# Master.net
KiCad netlist of a schematic drawn in Altium Designer
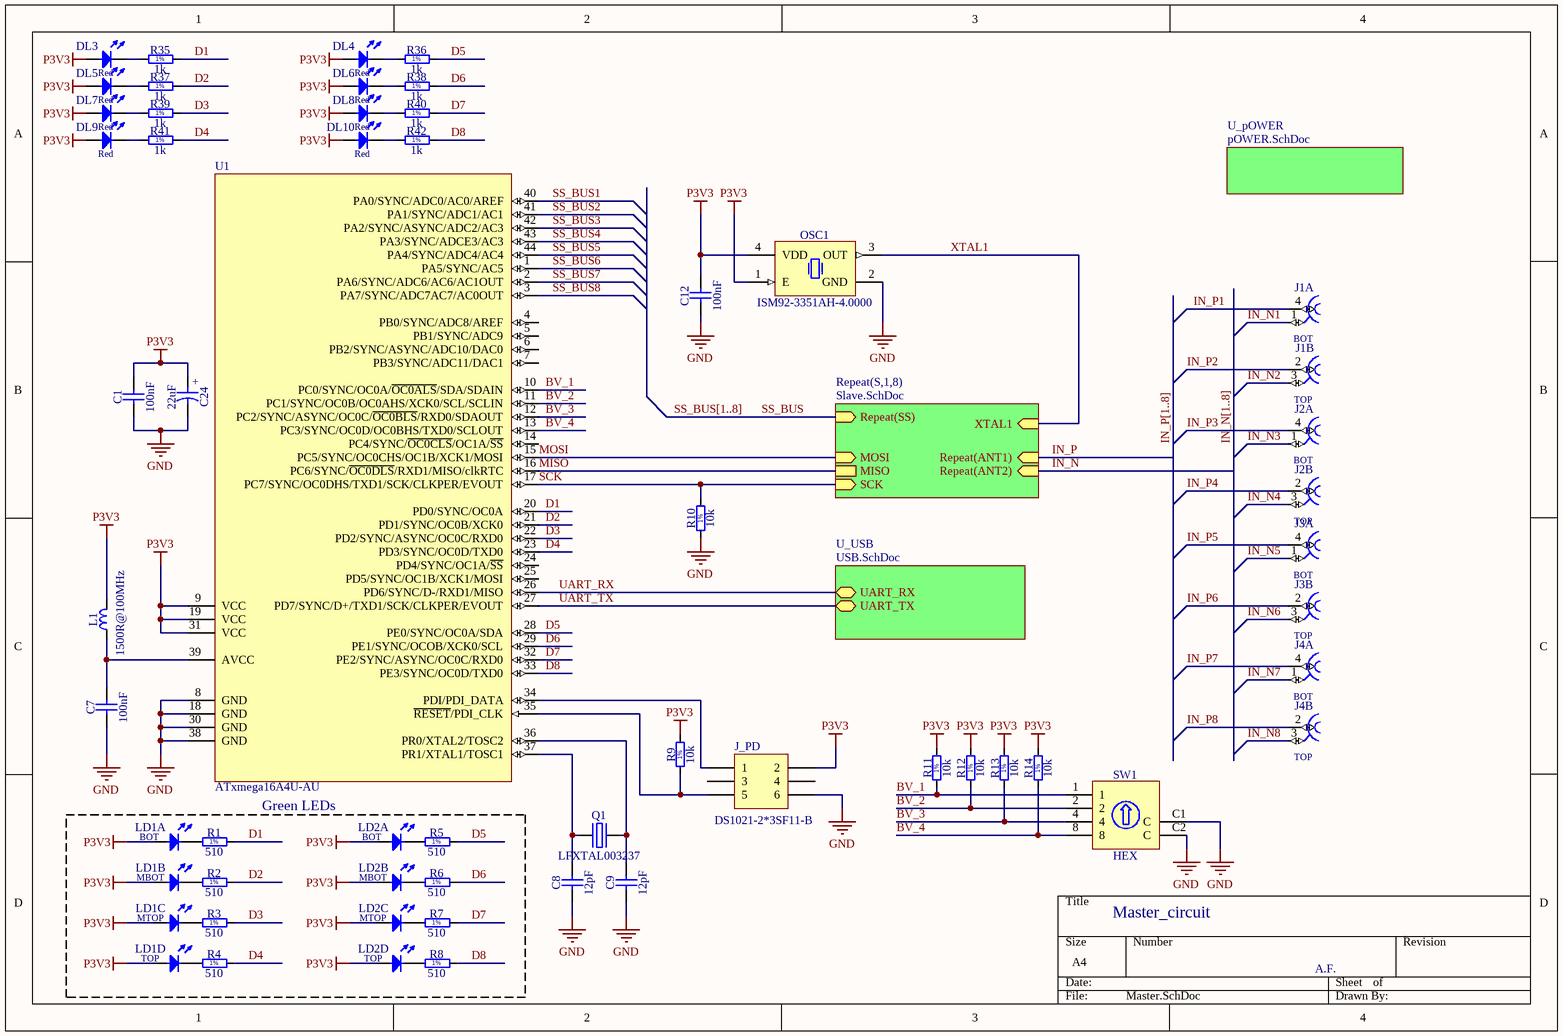
[diagram p0: Master.SchDoc]

(export (version "E")
  (design (tool "Eeschema 10.0.6"))
  (components
    (comp (ref "C1")
      (value "100nF")
      (footprint "CAPC1608X87N")
      (description "Non-polarised capacitor")
      (fields
        (field (name "PART NUMBER") "CC0603_100NF_50V_10%_X5R")
        (field (name "VOLTAGE") "50V")
        (field (name "AUTHOR") "CERN DEM MR")
      )
      (libsource (lib "Capacitors") (part "Capacitor - non polarized"))
    )
    (comp (ref "C7")
      (value "100nF")
      (footprint "CAPC1608X87N")
      (description "Non-polarised capacitor")
      (fields
        (field (name "PART NUMBER") "CC0603_100NF_50V_10%_X5R")
        (field (name "VOLTAGE") "50V")
        (field (name "AUTHOR") "CERN DEM MR")
      )
      (libsource (lib "Capacitors") (part "Capacitor - non polarized"))
    )
    (comp (ref "C8")
      (value "12pF")
      (footprint "CAPC1608X87N")
      (description "Non-polarised capacitor")
      (fields
        (field (name "PART NUMBER") "CC0603_12PF_50V_5%_NP0")
        (field (name "VOLTAGE") "50V")
        (field (name "AUTHOR") "CERN DEM JLC")
      )
      (libsource (lib "Capacitors") (part "Capacitor - non polarized"))
    )
    (comp (ref "C9")
      (value "12pF")
      (footprint "CAPC1608X87N")
      (description "Non-polarised capacitor")
      (fields
        (field (name "PART NUMBER") "CC0603_12PF_50V_5%_NP0")
        (field (name "VOLTAGE") "50V")
        (field (name "AUTHOR") "CERN DEM JLC")
      )
      (libsource (lib "Capacitors") (part "Capacitor - non polarized"))
    )
    (comp (ref "C12")
      (value "100nF")
      (footprint "CAPC1608X87N")
      (description "Non-polarised capacitor")
      (fields
        (field (name "PART NUMBER") "CC0603_100NF_50V_10%_X5R")
        (field (name "VOLTAGE") "50V")
        (field (name "AUTHOR") "CERN DEM MR")
      )
      (libsource (lib "Capacitors") (part "Capacitor - non polarized"))
    )
    (comp (ref "C24")
      (value "22uF")
      (footprint "CAPAE430X540N")
      (description "Polarised capacitor")
      (fields
        (field (name "PART NUMBER") "CAE430-540_22UF_10V_20%")
        (field (name "VOLTAGE") "10V")
        (field (name "AUTHOR") "CERN DEM JLC")
      )
      (libsource (lib "Capacitors") (part "Capacitor - polarized"))
    )
    (comp (ref "DL3")
      (value "Red")
      (footprint "LED_OSRAM_LSR976")
      (description "LED Red 1C 2A")
      (fields
        (field (name "PART NUMBER") "LS R976-NR-1")
        (field (name "MANUFACTURER") "OSRAM")
        (field (name "AUTHOR") "CERN DEM JLC")
      )
      (libsource (lib "ICs And Semiconductors") (part "LED Red 1C 2A"))
    )
    (comp (ref "DL4")
      (value "Red")
      (footprint "LED_OSRAM_LSR976")
      (description "LED Red 1C 2A")
      (fields
        (field (name "PART NUMBER") "LS R976-NR-1")
        (field (name "MANUFACTURER") "OSRAM")
        (field (name "AUTHOR") "CERN DEM JLC")
      )
      (libsource (lib "ICs And Semiconductors") (part "LED Red 1C 2A"))
    )
    (comp (ref "DL5")
      (value "Red")
      (footprint "LED_OSRAM_LSR976")
      (description "LED Red 1C 2A")
      (fields
        (field (name "PART NUMBER") "LS R976-NR-1")
        (field (name "MANUFACTURER") "OSRAM")
        (field (name "AUTHOR") "CERN DEM JLC")
      )
      (libsource (lib "ICs And Semiconductors") (part "LED Red 1C 2A"))
    )
    (comp (ref "DL6")
      (value "Red")
      (footprint "LED_OSRAM_LSR976")
      (description "LED Red 1C 2A")
      (fields
        (field (name "PART NUMBER") "LS R976-NR-1")
        (field (name "MANUFACTURER") "OSRAM")
        (field (name "AUTHOR") "CERN DEM JLC")
      )
      (libsource (lib "ICs And Semiconductors") (part "LED Red 1C 2A"))
    )
    (comp (ref "DL7")
      (value "Red")
      (footprint "LED_OSRAM_LSR976")
      (description "LED Red 1C 2A")
      (fields
        (field (name "PART NUMBER") "LS R976-NR-1")
        (field (name "MANUFACTURER") "OSRAM")
        (field (name "AUTHOR") "CERN DEM JLC")
      )
      (libsource (lib "ICs And Semiconductors") (part "LED Red 1C 2A"))
    )
    (comp (ref "DL8")
      (value "Red")
      (footprint "LED_OSRAM_LSR976")
      (description "LED Red 1C 2A")
      (fields
        (field (name "PART NUMBER") "LS R976-NR-1")
        (field (name "MANUFACTURER") "OSRAM")
        (field (name "AUTHOR") "CERN DEM JLC")
      )
      (libsource (lib "ICs And Semiconductors") (part "LED Red 1C 2A"))
    )
    (comp (ref "DL9")
      (value "Red")
      (footprint "LED_OSRAM_LSR976")
      (description "LED Red 1C 2A")
      (fields
        (field (name "PART NUMBER") "LS R976-NR-1")
        (field (name "MANUFACTURER") "OSRAM")
        (field (name "AUTHOR") "CERN DEM JLC")
      )
      (libsource (lib "ICs And Semiconductors") (part "LED Red 1C 2A"))
    )
    (comp (ref "DL10")
      (value "Red")
      (footprint "LED_OSRAM_LSR976")
      (description "LED Red 1C 2A")
      (fields
        (field (name "PART NUMBER") "LS R976-NR-1")
        (field (name "MANUFACTURER") "OSRAM")
        (field (name "AUTHOR") "CERN DEM JLC")
      )
      (libsource (lib "ICs And Semiconductors") (part "LED Red 1C 2A"))
    )
    (comp (ref "J1")
      (value "Family")
      (footprint "RENHOTEC_RHT-610-0049")
      (description "Dual Right Angle 50 Ohm BNC Jack, White Valox Case")
      (fields
        (field (name "PART NUMBER") "RENHOTEC_RHT-610-0049")
        (field (name "MANUFACTURER") "RENHOTEC")
        (field (name "AUTHOR") "GK")
      )
      (libsource (lib "LIBRARY_SCH") (part "CON_BNC_DUAL"))
    )
    (comp (ref "J2")
      (value "Family")
      (footprint "RENHOTEC_RHT-610-0049")
      (description "Dual Right Angle 50 Ohm BNC Jack, White Valox Case")
      (fields
        (field (name "PART NUMBER") "RENHOTEC_RHT-610-0049")
        (field (name "MANUFACTURER") "RENHOTEC")
        (field (name "AUTHOR") "GK")
      )
      (libsource (lib "LIBRARY_SCH") (part "CON_BNC_DUAL"))
    )
    (comp (ref "J3")
      (value "Family")
      (footprint "RENHOTEC_RHT-610-0049")
      (description "Dual Right Angle 50 Ohm BNC Jack, White Valox Case")
      (fields
        (field (name "PART NUMBER") "RENHOTEC_RHT-610-0049")
        (field (name "MANUFACTURER") "RENHOTEC")
        (field (name "AUTHOR") "GK")
      )
      (libsource (lib "LIBRARY_SCH") (part "CON_BNC_DUAL"))
    )
    (comp (ref "J4")
      (value "Family")
      (footprint "RENHOTEC_RHT-610-0049")
      (description "Dual Right Angle 50 Ohm BNC Jack, White Valox Case")
      (fields
        (field (name "PART NUMBER") "RENHOTEC_RHT-610-0049")
        (field (name "MANUFACTURER") "RENHOTEC")
        (field (name "AUTHOR") "GK")
      )
      (libsource (lib "LIBRARY_SCH") (part "CON_BNC_DUAL"))
    )
    (comp (ref "J_PD")
      (value "DS1021-2*3SF11-B")
      (footprint "HDR2X3")
      (description "THT Header, 6-Pin, Dual row, 2.54mm pitch")
      (fields (field (name "MANUFACTURER") "CONNFLY") (field (name "PUBLISHER") "Altium Limited"))
      (libsource (lib "Miscellaneous Connectors") (part "Header 3X2"))
    )
    (comp (ref "L1")
      (value "1500R@100MHz")
      (footprint "Miscellaneous Devices:1608[0603]")
      (description "Ferrite Bead")
      (fields
        (field (name "POWER") "0.5A")
        (field (name "MANUFACTURER") "MURATA")
        (field (name "AUTHOR") "CERN DEM BC")
      )
      (libsource (lib "altium-import") (part "root_1_Inductor_"))
    )
    (comp (ref "LD1")
      (value "H485CGDL")
      (footprint "LED_BIVAR_H485CGDL")
      (description "=Part Description")
      (fields (field (name "MANUFACTURER") "BIVAR") (field (name "AUTHOR") "CERN DEM JLC"))
      (libsource (lib "RFID_system") (part "LED x4 Green 1C2A-BOT_3C4A_5C6A_7C8A-TOP"))
    )
    (comp (ref "LD2")
      (value "H485CGDL")
      (footprint "LED_BIVAR_H485CGDL")
      (description "=Part Description")
      (fields (field (name "MANUFACTURER") "BIVAR") (field (name "AUTHOR") "CERN DEM JLC"))
      (libsource (lib "RFID_system") (part "LED x4 Green 1C2A-BOT_3C4A_5C6A_7C8A-TOP"))
    )
    (comp (ref "OSC1")
      (value "ISM92-3351AH-4.0000")
      (footprint "OSCSC250P320X500X130-4N")
      (description "Oscillator 4 pins 3.3V 4MHz")
      (fields (field (name "MANUFACTURER") "ILSI"))
      (libsource (lib "Crystals & Oscillators") (part "Oscillator 1E 2GND 3OUT 4VDD"))
    )
    (comp (ref "Q1")
      (value "LFXTAL003237")
      (footprint "XTAL1160X490X430")
      (description "=Part Description")
      (fields
        (field (name "MANUFACTURER") "IQD FREQUENCY PRODUCTS")
        (field (name "MANUFACTURER PART NUMBER") "LF XTAL003237")
        (field (name "AUTHOR") "CERN DEM MR")
      )
      (libsource (lib "ICs And Semiconductors") (part "Quartz Crystal"))
    )
    (comp (ref "R1")
      (value "510")
      (footprint "RESC1608X55N")
      (description "Resistor - 1%")
      (fields
        (field (name "PART NUMBER") "R0603_510R_1%_0.1W_100PPM")
        (field (name "POWER") "0.1W")
        (field (name "AUTHOR") "CERN DEM JLC")
      )
      (libsource (lib "Resistors") (part "Resistor - 1%"))
    )
    (comp (ref "R2")
      (value "510")
      (footprint "RESC1608X55N")
      (description "Resistor - 1%")
      (fields
        (field (name "PART NUMBER") "R0603_510R_1%_0.1W_100PPM")
        (field (name "POWER") "0.1W")
        (field (name "AUTHOR") "CERN DEM JLC")
      )
      (libsource (lib "Resistors") (part "Resistor - 1%"))
    )
    (comp (ref "R3")
      (value "510")
      (footprint "RESC1608X55N")
      (description "Resistor - 1%")
      (fields
        (field (name "PART NUMBER") "R0603_510R_1%_0.1W_100PPM")
        (field (name "POWER") "0.1W")
        (field (name "AUTHOR") "CERN DEM JLC")
      )
      (libsource (lib "Resistors") (part "Resistor - 1%"))
    )
    (comp (ref "R4")
      (value "510")
      (footprint "RESC1608X55N")
      (description "Resistor - 1%")
      (fields
        (field (name "PART NUMBER") "R0603_510R_1%_0.1W_100PPM")
        (field (name "POWER") "0.1W")
        (field (name "AUTHOR") "CERN DEM JLC")
      )
      (libsource (lib "Resistors") (part "Resistor - 1%"))
    )
    (comp (ref "R5")
      (value "510")
      (footprint "RESC1608X55N")
      (description "Resistor - 1%")
      (fields
        (field (name "PART NUMBER") "R0603_510R_1%_0.1W_100PPM")
        (field (name "POWER") "0.1W")
        (field (name "AUTHOR") "CERN DEM JLC")
      )
      (libsource (lib "Resistors") (part "Resistor - 1%"))
    )
    (comp (ref "R6")
      (value "510")
      (footprint "RESC1608X55N")
      (description "Resistor - 1%")
      (fields
        (field (name "PART NUMBER") "R0603_510R_1%_0.1W_100PPM")
        (field (name "POWER") "0.1W")
        (field (name "AUTHOR") "CERN DEM JLC")
      )
      (libsource (lib "Resistors") (part "Resistor - 1%"))
    )
    (comp (ref "R7")
      (value "510")
      (footprint "RESC1608X55N")
      (description "Resistor - 1%")
      (fields
        (field (name "PART NUMBER") "R0603_510R_1%_0.1W_100PPM")
        (field (name "POWER") "0.1W")
        (field (name "AUTHOR") "CERN DEM JLC")
      )
      (libsource (lib "Resistors") (part "Resistor - 1%"))
    )
    (comp (ref "R8")
      (value "510")
      (footprint "RESC1608X55N")
      (description "Resistor - 1%")
      (fields
        (field (name "PART NUMBER") "R0603_510R_1%_0.1W_100PPM")
        (field (name "POWER") "0.1W")
        (field (name "AUTHOR") "CERN DEM JLC")
      )
      (libsource (lib "Resistors") (part "Resistor - 1%"))
    )
    (comp (ref "R9")
      (value "10k")
      (footprint "RESC1608X55N")
      (description "Resistor - 1%")
      (fields
        (field (name "PART NUMBER") "R0603_10K_1%_0.1W_100PPM")
        (field (name "POWER") "0.1W")
        (field (name "AUTHOR") "CERN DEM JLC")
      )
      (libsource (lib "Resistors") (part "Resistor - 1%"))
    )
    (comp (ref "R10")
      (value "10k")
      (footprint "RESC1608X55N")
      (description "Resistor - 1%")
      (fields
        (field (name "PART NUMBER") "R0603_10K_1%_0.1W_100PPM")
        (field (name "POWER") "0.1W")
        (field (name "AUTHOR") "CERN DEM JLC")
      )
      (libsource (lib "Resistors") (part "Resistor - 1%"))
    )
    (comp (ref "R11")
      (value "10k")
      (footprint "RESC1608X55N")
      (description "Resistor - 1%")
      (fields
        (field (name "PART NUMBER") "R0603_10K_1%_0.1W_100PPM")
        (field (name "POWER") "0.1W")
        (field (name "AUTHOR") "CERN DEM JLC")
      )
      (libsource (lib "Resistors") (part "Resistor - 1%"))
    )
    (comp (ref "R12")
      (value "10k")
      (footprint "RESC1608X55N")
      (description "Resistor - 1%")
      (fields
        (field (name "PART NUMBER") "R0603_10K_1%_0.1W_100PPM")
        (field (name "POWER") "0.1W")
        (field (name "AUTHOR") "CERN DEM JLC")
      )
      (libsource (lib "Resistors") (part "Resistor - 1%"))
    )
    (comp (ref "R13")
      (value "10k")
      (footprint "RESC1608X55N")
      (description "Resistor - 1%")
      (fields
        (field (name "PART NUMBER") "R0603_10K_1%_0.1W_100PPM")
        (field (name "POWER") "0.1W")
        (field (name "AUTHOR") "CERN DEM JLC")
      )
      (libsource (lib "Resistors") (part "Resistor - 1%"))
    )
    (comp (ref "R14")
      (value "10k")
      (footprint "RESC1608X55N")
      (description "Resistor - 1%")
      (fields
        (field (name "PART NUMBER") "R0603_10K_1%_0.1W_100PPM")
        (field (name "POWER") "0.1W")
        (field (name "AUTHOR") "CERN DEM JLC")
      )
      (libsource (lib "Resistors") (part "Resistor - 1%"))
    )
    (comp (ref "R35")
      (value "1k")
      (footprint "RESC1608X50N")
      (description "Resistor - 1%")
      (fields
        (field (name "PART NUMBER") "R0805_1K_1%_0.33W_100PPM_VISHAY_CRCW-HP")
        (field (name "POWER") "0.33W")
        (field (name "AUTHOR") "CERN DEM JLC")
      )
      (libsource (lib "Resistors") (part "Resistor - 1%"))
    )
    (comp (ref "R36")
      (value "1k")
      (footprint "RESC1608X50N")
      (description "Resistor - 1%")
      (fields
        (field (name "PART NUMBER") "R0805_1K_1%_0.33W_100PPM_VISHAY_CRCW-HP")
        (field (name "POWER") "0.33W")
        (field (name "AUTHOR") "CERN DEM JLC")
      )
      (libsource (lib "Resistors") (part "Resistor - 1%"))
    )
    (comp (ref "R37")
      (value "1k")
      (footprint "RESC1608X50N")
      (description "Resistor - 1%")
      (fields
        (field (name "PART NUMBER") "R0805_1K_1%_0.33W_100PPM_VISHAY_CRCW-HP")
        (field (name "POWER") "0.33W")
        (field (name "AUTHOR") "CERN DEM JLC")
      )
      (libsource (lib "Resistors") (part "Resistor - 1%"))
    )
    (comp (ref "R38")
      (value "1k")
      (footprint "RESC1608X50N")
      (description "Resistor - 1%")
      (fields
        (field (name "PART NUMBER") "R0805_1K_1%_0.33W_100PPM_VISHAY_CRCW-HP")
        (field (name "POWER") "0.33W")
        (field (name "AUTHOR") "CERN DEM JLC")
      )
      (libsource (lib "Resistors") (part "Resistor - 1%"))
    )
    (comp (ref "R39")
      (value "1k")
      (footprint "RESC1608X50N")
      (description "Resistor - 1%")
      (fields
        (field (name "PART NUMBER") "R0805_1K_1%_0.33W_100PPM_VISHAY_CRCW-HP")
        (field (name "POWER") "0.33W")
        (field (name "AUTHOR") "CERN DEM JLC")
      )
      (libsource (lib "Resistors") (part "Resistor - 1%"))
    )
    (comp (ref "R40")
      (value "1k")
      (footprint "RESC1608X50N")
      (description "Resistor - 1%")
      (fields
        (field (name "PART NUMBER") "R0805_1K_1%_0.33W_100PPM_VISHAY_CRCW-HP")
        (field (name "POWER") "0.33W")
        (field (name "AUTHOR") "CERN DEM JLC")
      )
      (libsource (lib "Resistors") (part "Resistor - 1%"))
    )
    (comp (ref "R41")
      (value "1k")
      (footprint "RESC1608X50N")
      (description "Resistor - 1%")
      (fields
        (field (name "PART NUMBER") "R0805_1K_1%_0.33W_100PPM_VISHAY_CRCW-HP")
        (field (name "POWER") "0.33W")
        (field (name "AUTHOR") "CERN DEM JLC")
      )
      (libsource (lib "Resistors") (part "Resistor - 1%"))
    )
    (comp (ref "R42")
      (value "1k")
      (footprint "RESC1608X50N")
      (description "Resistor - 1%")
      (fields
        (field (name "PART NUMBER") "R0805_1K_1%_0.33W_100PPM_VISHAY_CRCW-HP")
        (field (name "POWER") "0.33W")
        (field (name "AUTHOR") "CERN DEM JLC")
      )
      (libsource (lib "Resistors") (part "Resistor - 1%"))
    )
    (comp (ref "SW1")
      (value "HEX")
      (footprint "SW_OMRON_A6RV-162RF")
      (description "Rotary Code Switch 1 2 4 8 C1 C2")
      (fields
        (field (name "PART NUMBER") "A6RV-162RF or ERD716RR")
        (field (name "MANUFACTURER") "OMRON")
        (field (name "AUTHOR") "CERN DEM JLC")
      )
      (libsource (lib "Eletro-mechanical") (part "SW Rotary 1 2 4 8 C1 C2"))
    )
    (comp (ref "U1")
      (value "ATxmega16A4U-AU")
      (footprint "44A_N")
      (fields
        (field (name "PART NUMBER") "ATXMEGA16A4-AU")
        (field (name "MANUFACTURER") "Microchip Technology")
      )
      (libsource (lib "RFID_system_atxmegau") (part "ATxmega16A4-AU"))
    )
  )
  (nets
    (net (code "2") (name "/BV_1") (class "Default")
      (node (ref "R11") (pin "1") (pinfunction "1_1") (pintype "passive"))
      (node (ref "SW1") (pin "1") (pinfunction "1_1") (pintype "passive"))
      (node (ref "U1") (pin "10") (pinfunction "PC0/SYNC/OC0A/~{OC0ALS}/SDA/SDAIN_10") (pintype "bidirectional"))
    )
    (net (code "3") (name "/BV_2") (class "Default")
      (node (ref "R12") (pin "1") (pinfunction "1_1") (pintype "passive"))
      (node (ref "SW1") (pin "2") (pinfunction "2_2") (pintype "passive"))
      (node (ref "U1") (pin "11") (pinfunction "PC1/SYNC/OC0B/OC0AHS/XCK0/SCL/SCLIN_11") (pintype "bidirectional"))
    )
    (net (code "4") (name "/BV_3") (class "Default")
      (node (ref "R13") (pin "1") (pinfunction "1_1") (pintype "passive"))
      (node (ref "SW1") (pin "4") (pinfunction "4_4") (pintype "passive"))
      (node (ref "U1") (pin "12") (pinfunction "PC2/SYNC/ASYNC/OC0C/~{OC0BLS}/RXD0/SDAOUT_12") (pintype "bidirectional"))
    )
    (net (code "5") (name "/BV_4") (class "Default")
      (node (ref "R14") (pin "1") (pinfunction "1_1") (pintype "passive"))
      (node (ref "SW1") (pin "8") (pinfunction "8_8") (pintype "passive"))
      (node (ref "U1") (pin "13") (pinfunction "PC3/SYNC/OC0D/OC0BHS/TXD0/SCLOUT_13") (pintype "bidirectional"))
    )
    (net (code "6") (name "/D1") (class "Default")
      (node (ref "R1") (pin "2") (pinfunction "2_2") (pintype "passive"))
      (node (ref "R35") (pin "1") (pinfunction "1_1") (pintype "passive"))
      (node (ref "U1") (pin "20") (pinfunction "PD0/SYNC/OC0A_20") (pintype "bidirectional"))
    )
    (net (code "7") (name "/D2") (class "Default")
      (node (ref "R2") (pin "2") (pinfunction "2_2") (pintype "passive"))
      (node (ref "R37") (pin "1") (pinfunction "1_1") (pintype "passive"))
      (node (ref "U1") (pin "21") (pinfunction "PD1/SYNC/OC0B/XCK0_21") (pintype "bidirectional"))
    )
    (net (code "8") (name "/D3") (class "Default")
      (node (ref "R3") (pin "2") (pinfunction "2_2") (pintype "passive"))
      (node (ref "R39") (pin "1") (pinfunction "1_1") (pintype "passive"))
      (node (ref "U1") (pin "22") (pinfunction "PD2/SYNC/ASYNC/OC0C/RXD0_22") (pintype "bidirectional"))
    )
    (net (code "9") (name "/D4") (class "Default")
      (node (ref "R4") (pin "2") (pinfunction "2_2") (pintype "passive"))
      (node (ref "R41") (pin "1") (pinfunction "1_1") (pintype "passive"))
      (node (ref "U1") (pin "23") (pinfunction "PD3/SYNC/OC0D/TXD0_23") (pintype "bidirectional"))
    )
    (net (code "10") (name "/D5") (class "Default")
      (node (ref "R36") (pin "1") (pinfunction "1_1") (pintype "passive"))
      (node (ref "R5") (pin "2") (pinfunction "2_2") (pintype "passive"))
      (node (ref "U1") (pin "28") (pinfunction "PE0/SYNC/OC0A/SDA_28") (pintype "bidirectional"))
    )
    (net (code "11") (name "/D6") (class "Default")
      (node (ref "R38") (pin "1") (pinfunction "1_1") (pintype "passive"))
      (node (ref "R6") (pin "2") (pinfunction "2_2") (pintype "passive"))
      (node (ref "U1") (pin "29") (pinfunction "PE1/SYNC/OCOB/XCK0/SCL_29") (pintype "bidirectional"))
    )
    (net (code "12") (name "/D7") (class "Default")
      (node (ref "R40") (pin "1") (pinfunction "1_1") (pintype "passive"))
      (node (ref "R7") (pin "2") (pinfunction "2_2") (pintype "passive"))
      (node (ref "U1") (pin "32") (pinfunction "PE2/SYNC/ASYNC/OC0C/RXD0_32") (pintype "bidirectional"))
    )
    (net (code "13") (name "/D8") (class "Default")
      (node (ref "R42") (pin "1") (pinfunction "1_1") (pintype "passive"))
      (node (ref "R8") (pin "2") (pinfunction "2_2") (pintype "passive"))
      (node (ref "U1") (pin "33") (pinfunction "PE3/SYNC/OC0D/TXD0_33") (pintype "bidirectional"))
    )
    (net (code "15") (name "/IN_N1") (class "Default")
      (node (ref "J1") (pin "1") (pinfunction "1_1") (pintype "bidirectional"))
    )
    (net (code "16") (name "/IN_N2") (class "Default")
      (node (ref "J1") (pin "3") (pinfunction "3_3") (pintype "bidirectional"))
    )
    (net (code "17") (name "/IN_N3") (class "Default")
      (node (ref "J2") (pin "1") (pinfunction "1_1") (pintype "bidirectional"))
    )
    (net (code "18") (name "/IN_N4") (class "Default")
      (node (ref "J2") (pin "3") (pinfunction "3_3") (pintype "bidirectional"))
    )
    (net (code "19") (name "/IN_N5") (class "Default")
      (node (ref "J3") (pin "1") (pinfunction "1_1") (pintype "bidirectional"))
    )
    (net (code "20") (name "/IN_N6") (class "Default")
      (node (ref "J3") (pin "3") (pinfunction "3_3") (pintype "bidirectional"))
    )
    (net (code "21") (name "/IN_N7") (class "Default")
      (node (ref "J4") (pin "1") (pinfunction "1_1") (pintype "bidirectional"))
    )
    (net (code "22") (name "/IN_N8") (class "Default")
      (node (ref "J4") (pin "3") (pinfunction "3_3") (pintype "bidirectional"))
    )
    (net (code "25") (name "/IN_P1") (class "Default")
      (node (ref "J1") (pin "4") (pinfunction "4_4") (pintype "bidirectional"))
    )
    (net (code "26") (name "/IN_P2") (class "Default")
      (node (ref "J1") (pin "2") (pinfunction "2_2") (pintype "bidirectional"))
    )
    (net (code "27") (name "/IN_P3") (class "Default")
      (node (ref "J2") (pin "4") (pinfunction "4_4") (pintype "bidirectional"))
    )
    (net (code "28") (name "/IN_P4") (class "Default")
      (node (ref "J2") (pin "2") (pinfunction "2_2") (pintype "bidirectional"))
    )
    (net (code "29") (name "/IN_P5") (class "Default")
      (node (ref "J3") (pin "4") (pinfunction "4_4") (pintype "bidirectional"))
    )
    (net (code "30") (name "/IN_P6") (class "Default")
      (node (ref "J3") (pin "2") (pinfunction "2_2") (pintype "bidirectional"))
    )
    (net (code "31") (name "/IN_P7") (class "Default")
      (node (ref "J4") (pin "4") (pinfunction "4_4") (pintype "bidirectional"))
    )
    (net (code "32") (name "/IN_P8") (class "Default")
      (node (ref "J4") (pin "2") (pinfunction "2_2") (pintype "bidirectional"))
    )
    (net (code "34") (name "/MISO") (class "Default")
      (node (ref "U1") (pin "16") (pinfunction "PC6/SYNC/~{OC0DLS}/RXD1/MISO/clkRTC_16") (pintype "bidirectional"))
    )
    (net (code "35") (name "/MOSI") (class "Default")
      (node (ref "U1") (pin "15") (pinfunction "PC5/SYNC/OC0CHS/OC1B/XCK1/MOSI_15") (pintype "bidirectional"))
    )
    (net (code "36") (name "/SCK") (class "Default")
      (node (ref "R10") (pin "2") (pinfunction "2_2") (pintype "passive"))
      (node (ref "U1") (pin "17") (pinfunction "PC7/SYNC/OC0DHS/TXD1/SCK/CLKPER/EVOUT_17") (pintype "bidirectional"))
    )
    (net (code "38") (name "/SS_BUS1") (class "Default")
      (node (ref "U1") (pin "40") (pinfunction "PA0/SYNC/ADC0/AC0/AREF_40") (pintype "bidirectional"))
    )
    (net (code "39") (name "/SS_BUS2") (class "Default")
      (node (ref "U1") (pin "41") (pinfunction "PA1/SYNC/ADC1/AC1_41") (pintype "bidirectional"))
    )
    (net (code "40") (name "/SS_BUS3") (class "Default")
      (node (ref "U1") (pin "42") (pinfunction "PA2/SYNC/ASYNC/ADC2/AC3_42") (pintype "bidirectional"))
    )
    (net (code "41") (name "/SS_BUS4") (class "Default")
      (node (ref "U1") (pin "43") (pinfunction "PA3/SYNC/ADCE3/AC3_43") (pintype "bidirectional"))
    )
    (net (code "42") (name "/SS_BUS5") (class "Default")
      (node (ref "U1") (pin "44") (pinfunction "PA4/SYNC/ADC4/AC4_44") (pintype "bidirectional"))
    )
    (net (code "43") (name "/SS_BUS6") (class "Default")
      (node (ref "U1") (pin "1") (pinfunction "PA5/SYNC/AC5_1") (pintype "bidirectional"))
    )
    (net (code "44") (name "/SS_BUS7") (class "Default")
      (node (ref "U1") (pin "2") (pinfunction "PA6/SYNC/ADC6/AC6/AC1OUT_2") (pintype "bidirectional"))
    )
    (net (code "45") (name "/SS_BUS8") (class "Default")
      (node (ref "U1") (pin "3") (pinfunction "PA7/SYNC/ADC7AC7/AC0OUT_3") (pintype "bidirectional"))
    )
    (net (code "47") (name "/UART_RX") (class "Default")
      (node (ref "U1") (pin "26") (pinfunction "PD6/SYNC/D-/RXD1/MISO_26") (pintype "bidirectional"))
    )
    (net (code "48") (name "/UART_TX") (class "Default")
      (node (ref "U1") (pin "27") (pinfunction "PD7/SYNC/D+/TXD1/SCK/CLKPER/EVOUT_27") (pintype "bidirectional"))
    )
    (net (code "49") (name "/XTAL1") (class "Default")
      (node (ref "OSC1") (pin "3") (pinfunction "OUT_3") (pintype "output"))
    )
    (net (code "50") (name "GND") (class "Default")
      (node (ref "C1") (pin "1") (pinfunction "1_1") (pintype "passive"))
      (node (ref "C12") (pin "1") (pinfunction "1_1") (pintype "passive"))
      (node (ref "C24") (pin "2") (pinfunction "2_2") (pintype "passive"))
      (node (ref "C7") (pin "1") (pinfunction "1_1") (pintype "passive"))
      (node (ref "C8") (pin "1") (pinfunction "1_1") (pintype "passive"))
      (node (ref "C9") (pin "1") (pinfunction "1_1") (pintype "passive"))
      (node (ref "J_PD") (pin "6") (pinfunction "6_6") (pintype "passive"))
      (node (ref "OSC1") (pin "2") (pinfunction "GND_2") (pintype "power_in"))
      (node (ref "R10") (pin "1") (pinfunction "1_1") (pintype "passive"))
      (node (ref "SW1") (pin "C1") (pinfunction "C_C1") (pintype "passive"))
      (node (ref "SW1") (pin "C2") (pinfunction "C_C2") (pintype "passive"))
      (node (ref "U1") (pin "18") (pinfunction "GND_18") (pintype "power_in"))
      (node (ref "U1") (pin "30") (pinfunction "GND_30") (pintype "power_in"))
      (node (ref "U1") (pin "38") (pinfunction "GND_38") (pintype "power_in"))
      (node (ref "U1") (pin "8") (pinfunction "GND_8") (pintype "power_in"))
    )
    (net (code "51") (name "Net-(DL3-C)") (class "Default")
      (node (ref "DL3") (pin "1") (pinfunction "C_1") (pintype "passive"))
      (node (ref "R35") (pin "2") (pinfunction "2_2") (pintype "passive"))
    )
    (net (code "52") (name "Net-(DL4-C)") (class "Default")
      (node (ref "DL4") (pin "1") (pinfunction "C_1") (pintype "passive"))
      (node (ref "R36") (pin "2") (pinfunction "2_2") (pintype "passive"))
    )
    (net (code "53") (name "Net-(DL5-C)") (class "Default")
      (node (ref "DL5") (pin "1") (pinfunction "C_1") (pintype "passive"))
      (node (ref "R37") (pin "2") (pinfunction "2_2") (pintype "passive"))
    )
    (net (code "54") (name "Net-(DL6-C)") (class "Default")
      (node (ref "DL6") (pin "1") (pinfunction "C_1") (pintype "passive"))
      (node (ref "R38") (pin "2") (pinfunction "2_2") (pintype "passive"))
    )
    (net (code "55") (name "Net-(DL7-C)") (class "Default")
      (node (ref "DL7") (pin "1") (pinfunction "C_1") (pintype "passive"))
      (node (ref "R39") (pin "2") (pinfunction "2_2") (pintype "passive"))
    )
    (net (code "56") (name "Net-(DL8-C)") (class "Default")
      (node (ref "DL8") (pin "1") (pinfunction "C_1") (pintype "passive"))
      (node (ref "R40") (pin "2") (pinfunction "2_2") (pintype "passive"))
    )
    (net (code "57") (name "Net-(DL9-C)") (class "Default")
      (node (ref "DL9") (pin "1") (pinfunction "C_1") (pintype "passive"))
      (node (ref "R41") (pin "2") (pinfunction "2_2") (pintype "passive"))
    )
    (net (code "58") (name "Net-(DL10-C)") (class "Default")
      (node (ref "DL10") (pin "1") (pinfunction "C_1") (pintype "passive"))
      (node (ref "R42") (pin "2") (pinfunction "2_2") (pintype "passive"))
    )
    (net (code "59") (name "Net-(LD1A-C)") (class "Default")
      (node (ref "LD1") (pin "1") (pinfunction "C_1") (pintype "passive"))
      (node (ref "R1") (pin "1") (pinfunction "1_1") (pintype "passive"))
    )
    (net (code "60") (name "Net-(LD1B-C)") (class "Default")
      (node (ref "LD1") (pin "3") (pinfunction "C_3") (pintype "passive"))
      (node (ref "R2") (pin "1") (pinfunction "1_1") (pintype "passive"))
    )
    (net (code "61") (name "Net-(LD1C-C)") (class "Default")
      (node (ref "LD1") (pin "5") (pinfunction "C_5") (pintype "passive"))
      (node (ref "R3") (pin "1") (pinfunction "1_1") (pintype "passive"))
    )
    (net (code "62") (name "Net-(LD1D-C)") (class "Default")
      (node (ref "LD1") (pin "7") (pinfunction "C_7") (pintype "passive"))
      (node (ref "R4") (pin "1") (pinfunction "1_1") (pintype "passive"))
    )
    (net (code "63") (name "Net-(LD2A-C)") (class "Default")
      (node (ref "LD2") (pin "1") (pinfunction "C_1") (pintype "passive"))
      (node (ref "R5") (pin "1") (pinfunction "1_1") (pintype "passive"))
    )
    (net (code "64") (name "Net-(LD2B-C)") (class "Default")
      (node (ref "LD2") (pin "3") (pinfunction "C_3") (pintype "passive"))
      (node (ref "R6") (pin "1") (pinfunction "1_1") (pintype "passive"))
    )
    (net (code "65") (name "Net-(LD2C-C)") (class "Default")
      (node (ref "LD2") (pin "5") (pinfunction "C_5") (pintype "passive"))
      (node (ref "R7") (pin "1") (pinfunction "1_1") (pintype "passive"))
    )
    (net (code "66") (name "Net-(LD2D-C)") (class "Default")
      (node (ref "LD2") (pin "7") (pinfunction "C_7") (pintype "passive"))
      (node (ref "R8") (pin "1") (pinfunction "1_1") (pintype "passive"))
    )
    (net (code "67") (name "Net-(Q1-OSC1)") (class "Default")
      (node (ref "C8") (pin "2") (pinfunction "2_2") (pintype "passive"))
      (node (ref "Q1") (pin "1") (pinfunction "OSC1_1") (pintype "passive"))
      (node (ref "U1") (pin "37") (pinfunction "PR1/XTAL1/TOSC1_37") (pintype "bidirectional"))
    )
    (net (code "68") (name "Net-(Q1-OSC2)") (class "Default")
      (node (ref "C9") (pin "2") (pinfunction "2_2") (pintype "passive"))
      (node (ref "Q1") (pin "2") (pinfunction "OSC2_2") (pintype "passive"))
      (node (ref "U1") (pin "36") (pinfunction "PR0/XTAL2/TOSC2_36") (pintype "bidirectional"))
    )
    (net (code "69") (name "Net-(U1-AVCC)") (class "Default")
      (node (ref "C7") (pin "2") (pinfunction "2_2") (pintype "passive"))
      (node (ref "L1") (pin "1") (pinfunction "1_1") (pintype "passive"))
      (node (ref "U1") (pin "39") (pinfunction "AVCC_39") (pintype "power_in"))
    )
    (net (code "70") (name "Net-(U1-PDI{slash}PDI_DATA)") (class "Default")
      (node (ref "J_PD") (pin "1") (pinfunction "1_1") (pintype "passive"))
      (node (ref "U1") (pin "34") (pinfunction "PDI/PDI_DATA_34") (pintype "bidirectional"))
    )
    (net (code "71") (name "Net-(U1-~{RESET}{slash}PDI_CLK)") (class "Default")
      (node (ref "J_PD") (pin "5") (pinfunction "5_5") (pintype "passive"))
      (node (ref "R9") (pin "1") (pinfunction "1_1") (pintype "passive"))
      (node (ref "U1") (pin "35") (pinfunction "~{RESET}/PDI_CLK_35") (pintype "input"))
    )
    (net (code "72") (name "P3V3") (class "Default")
      (node (ref "C1") (pin "2") (pinfunction "2_2") (pintype "passive"))
      (node (ref "C12") (pin "2") (pinfunction "2_2") (pintype "passive"))
      (node (ref "C24") (pin "1") (pinfunction "1_1") (pintype "passive"))
      (node (ref "DL10") (pin "2") (pinfunction "A_2") (pintype "passive"))
      (node (ref "DL3") (pin "2") (pinfunction "A_2") (pintype "passive"))
      (node (ref "DL4") (pin "2") (pinfunction "A_2") (pintype "passive"))
      (node (ref "DL5") (pin "2") (pinfunction "A_2") (pintype "passive"))
      (node (ref "DL6") (pin "2") (pinfunction "A_2") (pintype "passive"))
      (node (ref "DL7") (pin "2") (pinfunction "A_2") (pintype "passive"))
      (node (ref "DL8") (pin "2") (pinfunction "A_2") (pintype "passive"))
      (node (ref "DL9") (pin "2") (pinfunction "A_2") (pintype "passive"))
      (node (ref "J_PD") (pin "2") (pinfunction "2_2") (pintype "passive"))
      (node (ref "L1") (pin "2") (pinfunction "2_2") (pintype "passive"))
      (node (ref "LD1") (pin "2") (pinfunction "A_2") (pintype "passive"))
      (node (ref "LD1") (pin "4") (pinfunction "A_4") (pintype "passive"))
      (node (ref "LD1") (pin "6") (pinfunction "A_6") (pintype "passive"))
      (node (ref "LD1") (pin "8") (pinfunction "A_8") (pintype "passive"))
      (node (ref "LD2") (pin "2") (pinfunction "A_2") (pintype "passive"))
      (node (ref "LD2") (pin "4") (pinfunction "A_4") (pintype "passive"))
      (node (ref "LD2") (pin "6") (pinfunction "A_6") (pintype "passive"))
      (node (ref "LD2") (pin "8") (pinfunction "A_8") (pintype "passive"))
      (node (ref "OSC1") (pin "1") (pinfunction "E_1") (pintype "input"))
      (node (ref "OSC1") (pin "4") (pinfunction "VDD_4") (pintype "power_in"))
      (node (ref "R11") (pin "2") (pinfunction "2_2") (pintype "passive"))
      (node (ref "R12") (pin "2") (pinfunction "2_2") (pintype "passive"))
      (node (ref "R13") (pin "2") (pinfunction "2_2") (pintype "passive"))
      (node (ref "R14") (pin "2") (pinfunction "2_2") (pintype "passive"))
      (node (ref "R9") (pin "2") (pinfunction "2_2") (pintype "passive"))
      (node (ref "U1") (pin "19") (pinfunction "VCC_19") (pintype "power_in"))
      (node (ref "U1") (pin "31") (pinfunction "VCC_31") (pintype "power_in"))
      (node (ref "U1") (pin "9") (pinfunction "VCC_9") (pintype "power_in"))
    )
    (net (code "73") (name "unconnected-(J_PD-Pad3)") (class "Default")
      (node (ref "J_PD") (pin "3") (pinfunction "3_3") (pintype "passive"))
    )
    (net (code "74") (name "unconnected-(J_PD-Pad4)") (class "Default")
      (node (ref "J_PD") (pin "4") (pinfunction "4_4") (pintype "passive"))
    )
    (net (code "75") (name "unconnected-(U1-PB0{slash}SYNC{slash}ADC8{slash}AREF-Pad4)") (class "Default")
      (node (ref "U1") (pin "4") (pinfunction "PB0/SYNC/ADC8/AREF_4") (pintype "bidirectional"))
    )
    (net (code "76") (name "unconnected-(U1-PB1{slash}SYNC{slash}ADC9-Pad5)") (class "Default")
      (node (ref "U1") (pin "5") (pinfunction "PB1/SYNC/ADC9_5") (pintype "bidirectional"))
    )
    (net (code "77") (name "unconnected-(U1-PB2{slash}SYNC{slash}ASYNC{slash}ADC10{slash}DAC0-Pad6)") (class "Default")
      (node (ref "U1") (pin "6") (pinfunction "PB2/SYNC/ASYNC/ADC10/DAC0_6") (pintype "bidirectional"))
    )
    (net (code "78") (name "unconnected-(U1-PB3{slash}SYNC{slash}ADC11{slash}DAC1-Pad7)") (class "Default")
      (node (ref "U1") (pin "7") (pinfunction "PB3/SYNC/ADC11/DAC1_7") (pintype "bidirectional"))
    )
    (net (code "79") (name "unconnected-(U1-PC4{slash}SYNC{slash}~{OC0CLS}{slash}OC1A{slash}~{SS}-Pad14)") (class "Default")
      (node (ref "U1") (pin "14") (pinfunction "PC4/SYNC/~{OC0CLS}/OC1A/~{SS}_14") (pintype "bidirectional"))
    )
    (net (code "80") (name "unconnected-(U1-PD4{slash}SYNC{slash}OC1A{slash}~{SS}-Pad24)") (class "Default")
      (node (ref "U1") (pin "24") (pinfunction "PD4/SYNC/OC1A/~{SS}_24") (pintype "bidirectional"))
    )
    (net (code "81") (name "unconnected-(U1-PD5{slash}SYNC{slash}OC1B{slash}XCK1{slash}MOSI-Pad25)") (class "Default")
      (node (ref "U1") (pin "25") (pinfunction "PD5/SYNC/OC1B/XCK1/MOSI_25") (pintype "bidirectional"))
    )
  )
)
